# auto_F1.net
KiCad netlist of a schematic drawn in EAGLE
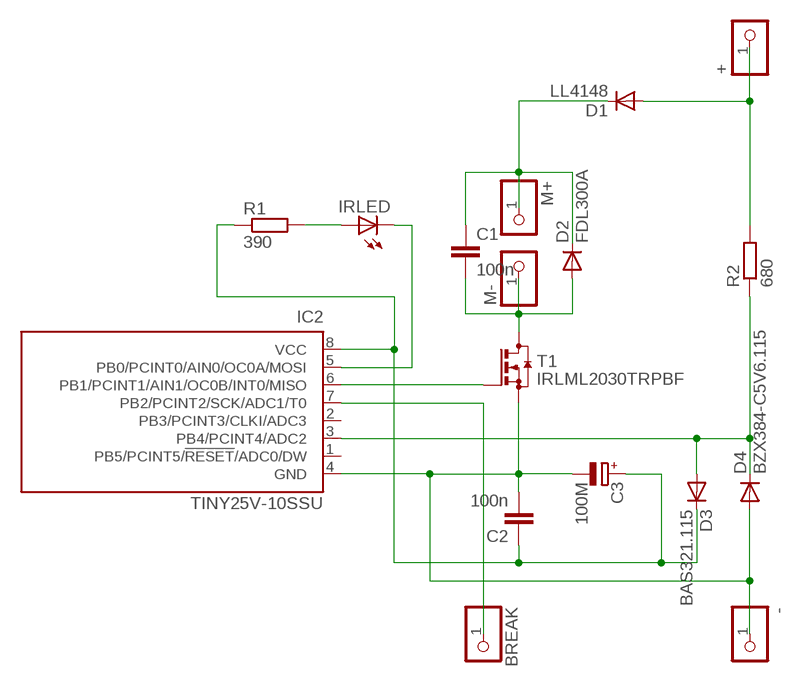
[diagram p0: schematic, sheet 1]

(export (version "E")
  (design (tool "Eeschema 10.0.6"))
  (components
    (comp (ref "+")
      (value "PINHD-1X1")
      (footprint "eagle-import:1X01")
      (libsource (lib "eagle-import") (part "PINHD-1X1"))
    )
    (comp (ref "-")
      (value "PINHD-1X1")
      (footprint "eagle-import:1X01")
      (libsource (lib "eagle-import") (part "PINHD-1X1"))
    )
    (comp (ref "BREAK")
      (value "PINHD-1X1")
      (footprint "eagle-import:1X01")
      (libsource (lib "eagle-import") (part "PINHD-1X1"))
    )
    (comp (ref "C1")
      (value "100n")
      (footprint "eagle-import:C1206")
      (libsource (lib "eagle-import") (part "C-EUC1206"))
    )
    (comp (ref "C2")
      (value "100n")
      (footprint "eagle-import:C1206")
      (libsource (lib "eagle-import") (part "C-EUC1206"))
    )
    (comp (ref "C3")
      (value "100M")
      (footprint "eagle-import:SMC_C")
      (libsource (lib "eagle-import") (part "CPOL-EUSMCC"))
    )
    (comp (ref "D1")
      (value "LL4148")
      (footprint "eagle-import:MINIMELF")
      (libsource (lib "eagle-import") (part "DIODE-MINIMELF"))
    )
    (comp (ref "D2")
      (value "FDL300A")
      (footprint "eagle-import:MINIMELF")
      (libsource (lib "eagle-import") (part "DIODE-MINIMELF"))
    )
    (comp (ref "D3")
      (value "BAS321.115")
      (footprint "eagle-import:MICROMELF-W")
      (libsource (lib "eagle-import") (part "DIODE-MICROMELF-W"))
    )
    (comp (ref "D4")
      (value "BZX384-C5V6.115")
      (footprint "eagle-import:MICROMELF-W")
      (libsource (lib "eagle-import") (part "DIODE-MICROMELF-W"))
    )
    (comp (ref "IC2")
      (value "TINY25V-10SSU")
      (footprint "eagle-import:8S1")
      (fields (field (name "MPN") "ATTINY13-20SSU"))
      (libsource (lib "eagle-import") (part "TINY13SSU-20"))
    )
    (comp (ref "IRLED")
      (value "LED3MM")
      (footprint "eagle-import:LED3MM")
      (libsource (lib "eagle-import") (part "LED3MM"))
    )
    (comp (ref "M+")
      (value "PINHD-1X1")
      (footprint "eagle-import:1X01")
      (libsource (lib "eagle-import") (part "PINHD-1X1"))
    )
    (comp (ref "M-")
      (value "PINHD-1X1")
      (footprint "eagle-import:1X01")
      (libsource (lib "eagle-import") (part "PINHD-1X1"))
    )
    (comp (ref "R1")
      (value "390")
      (footprint "eagle-import:R1206")
      (libsource (lib "eagle-import") (part "R-EU_R1206"))
    )
    (comp (ref "R2")
      (value "680")
      (footprint "eagle-import:R1206")
      (libsource (lib "eagle-import") (part "R-EU_R1206"))
    )
    (comp (ref "T1")
      (value "IRLML2030TRPBF")
      (footprint "eagle-import:SOT23")
      (libsource (lib "eagle-import") (part "BSS123"))
    )
  )
  (nets
    (net (code "1") (name "Net-(+-Pad1)") (class "Default")
      (node (ref "+") (pin "1") (pinfunction "1_1") (pintype "passive"))
      (node (ref "D1") (pin "A") (pinfunction "A_A") (pintype "passive"))
      (node (ref "R2") (pin "2") (pinfunction "2_2") (pintype "passive"))
    )
    (net (code "2") (name "Net-(C1-Pad1)") (class "Default")
      (node (ref "C1") (pin "1") (pinfunction "1_1") (pintype "passive"))
      (node (ref "D1") (pin "C") (pinfunction "C_C") (pintype "passive"))
      (node (ref "D2") (pin "C") (pinfunction "C_C") (pintype "passive"))
      (node (ref "M+") (pin "1") (pinfunction "1_1") (pintype "passive"))
    )
    (net (code "3") (name "Net-(IC2-GND)") (class "Default")
      (node (ref "-") (pin "1") (pinfunction "1_1") (pintype "passive"))
      (node (ref "C2") (pin "2") (pinfunction "2_2") (pintype "passive"))
      (node (ref "C3") (pin "-") (pinfunction "-_-") (pintype "passive"))
      (node (ref "D4") (pin "A") (pinfunction "A_A") (pintype "passive"))
      (node (ref "IC2") (pin "4") (pinfunction "GND_4") (pintype "power_in"))
      (node (ref "T1") (pin "2") (pinfunction "S_2") (pintype "passive"))
    )
    (net (code "4") (name "Net-(IC2-PB0{slash}PCINT0{slash}AIN0{slash}OC0A{slash}MOSI)") (class "Default")
      (node (ref "IC2") (pin "5") (pinfunction "PB0/PCINT0/AIN0/OC0A/MOSI_5") (pintype "bidirectional"))
      (node (ref "IRLED") (pin "K") (pinfunction "C_K") (pintype "passive"))
    )
    (net (code "5") (name "Net-(IC2-PB1{slash}PCINT1{slash}AIN1{slash}OC0B{slash}INT0{slash}MISO)") (class "Default")
      (node (ref "IC2") (pin "6") (pinfunction "PB1/PCINT1/AIN1/OC0B/INT0/MISO_6") (pintype "bidirectional"))
      (node (ref "T1") (pin "1") (pinfunction "G_1") (pintype "passive"))
    )
    (net (code "6") (name "Net-(IC2-PB2{slash}PCINT2{slash}SCK{slash}ADC1{slash}T0)") (class "Default")
      (node (ref "BREAK") (pin "1") (pinfunction "1_1") (pintype "passive"))
      (node (ref "IC2") (pin "7") (pinfunction "PB2/PCINT2/SCK/ADC1/T0_7") (pintype "bidirectional"))
    )
    (net (code "7") (name "Net-(IC2-PB4{slash}PCINT4{slash}ADC2)") (class "Default")
      (node (ref "D3") (pin "A") (pinfunction "A_A") (pintype "passive"))
      (node (ref "D4") (pin "C") (pinfunction "C_C") (pintype "passive"))
      (node (ref "IC2") (pin "3") (pinfunction "PB4/PCINT4/ADC2_3") (pintype "bidirectional"))
      (node (ref "R2") (pin "1") (pinfunction "1_1") (pintype "passive"))
    )
    (net (code "8") (name "Net-(IC2-VCC)") (class "Default")
      (node (ref "C2") (pin "1") (pinfunction "1_1") (pintype "passive"))
      (node (ref "C3") (pin "+") (pinfunction "+_+") (pintype "passive"))
      (node (ref "D3") (pin "C") (pinfunction "C_C") (pintype "passive"))
      (node (ref "IC2") (pin "8") (pinfunction "VCC_8") (pintype "power_in"))
      (node (ref "R1") (pin "1") (pinfunction "1_1") (pintype "passive"))
    )
    (net (code "9") (name "Net-(IRLED-PadA)") (class "Default")
      (node (ref "IRLED") (pin "A") (pinfunction "A_A") (pintype "passive"))
      (node (ref "R1") (pin "2") (pinfunction "2_2") (pintype "passive"))
    )
    (net (code "10") (name "Net-(T1-D)") (class "Default")
      (node (ref "C1") (pin "2") (pinfunction "2_2") (pintype "passive"))
      (node (ref "D2") (pin "A") (pinfunction "A_A") (pintype "passive"))
      (node (ref "M-") (pin "1") (pinfunction "1_1") (pintype "passive"))
      (node (ref "T1") (pin "3") (pinfunction "D_3") (pintype "passive"))
    )
    (net (code "11") (name "unconnected-(IC2-PB3{slash}PCINT3{slash}CLKI{slash}ADC3-Pad2)") (class "Default")
      (node (ref "IC2") (pin "2") (pinfunction "PB3/PCINT3/CLKI/ADC3_2") (pintype "bidirectional"))
    )
    (net (code "12") (name "unconnected-(IC2-PB5{slash}PCINT5{slash}~{RESET}{slash}ADC0{slash}DW-Pad1)") (class "Default")
      (node (ref "IC2") (pin "1") (pinfunction "PB5/PCINT5/~{RESET}/ADC0/DW_1") (pintype "bidirectional"))
    )
  )
)
